# Adafruit_OV5640_Breakout.net
KiCad netlist of a schematic drawn in EAGLE
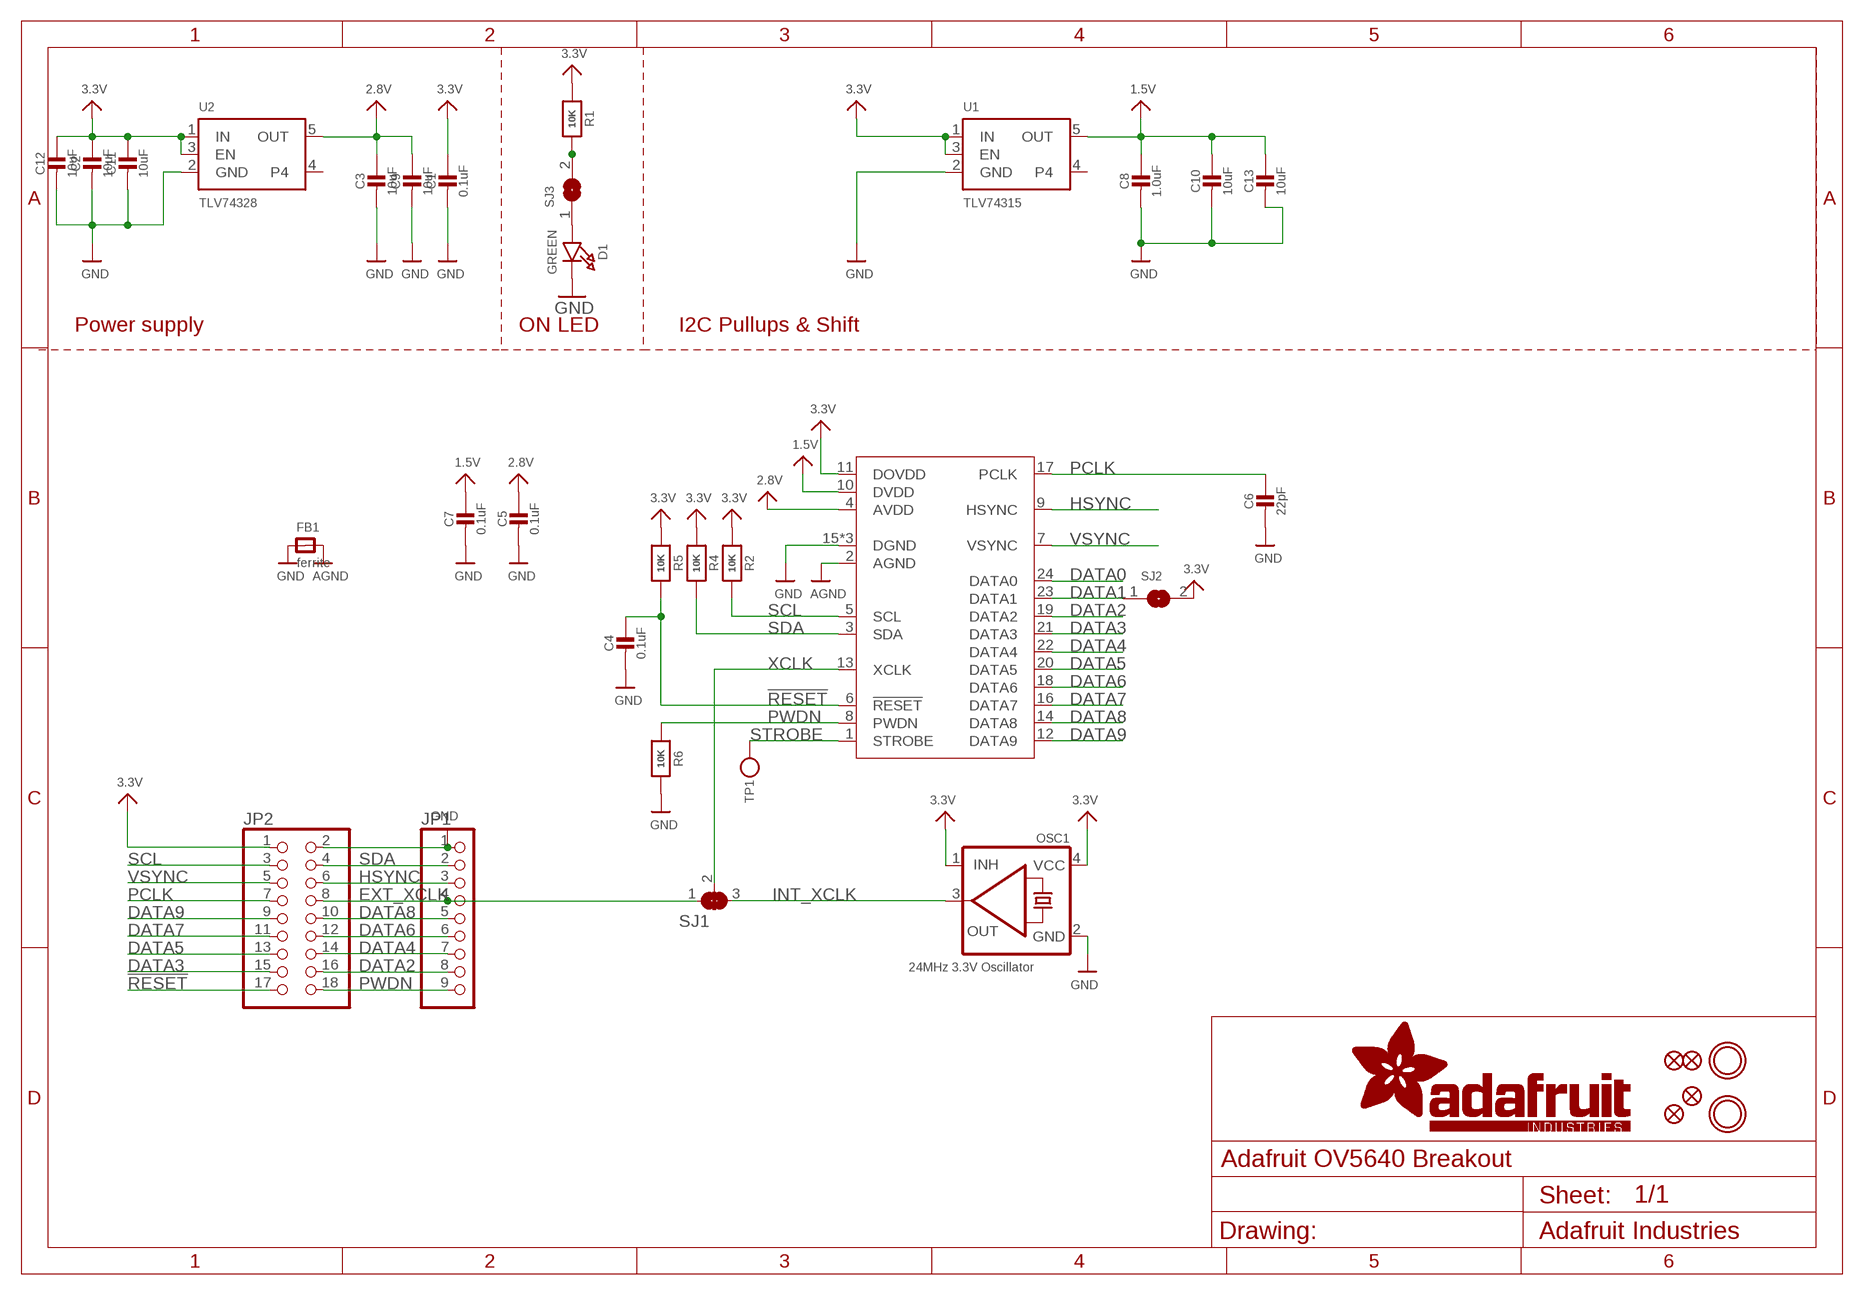
[diagram p0: schematic, sheet 1]

(export (version "E")
  (design (tool "Eeschema 10.0.6"))
  (components
    (comp (ref "C1")
      (value "0.1uF")
      (footprint "eagle-import:0603-NO")
      (libsource (lib "eagle-import") (part "CAP_CERAMIC0603_NO"))
    )
    (comp (ref "C2")
      (value "10uF")
      (footprint "eagle-import:0805-NO")
      (libsource (lib "eagle-import") (part "CAP_CERAMIC0805-NOOUTLINE"))
    )
    (comp (ref "C3")
      (value "10uF")
      (footprint "eagle-import:0805-NO")
      (libsource (lib "eagle-import") (part "CAP_CERAMIC0805-NOOUTLINE"))
    )
    (comp (ref "C4")
      (value "0.1uF")
      (footprint "eagle-import:0603-NO")
      (libsource (lib "eagle-import") (part "CAP_CERAMIC0603_NO"))
    )
    (comp (ref "C5")
      (value "0.1uF")
      (footprint "eagle-import:0603-NO")
      (libsource (lib "eagle-import") (part "CAP_CERAMIC0603_NO"))
    )
    (comp (ref "C6")
      (value "22pF")
      (footprint "eagle-import:0603-NO")
      (libsource (lib "eagle-import") (part "CAP_CERAMIC0603_NO"))
    )
    (comp (ref "C7")
      (value "0.1uF")
      (footprint "eagle-import:0603-NO")
      (libsource (lib "eagle-import") (part "CAP_CERAMIC0603_NO"))
    )
    (comp (ref "C8")
      (value "1.0uF")
      (footprint "eagle-import:0603-NO")
      (libsource (lib "eagle-import") (part "CAP_CERAMIC0603_NO"))
    )
    (comp (ref "C9")
      (value "10uF")
      (footprint "eagle-import:0805-NO")
      (libsource (lib "eagle-import") (part "CAP_CERAMIC0805-NOOUTLINE"))
    )
    (comp (ref "C10")
      (value "10uF")
      (footprint "eagle-import:0805-NO")
      (libsource (lib "eagle-import") (part "CAP_CERAMIC0805-NOOUTLINE"))
    )
    (comp (ref "C11")
      (value "10uF")
      (footprint "eagle-import:0805-NO")
      (libsource (lib "eagle-import") (part "CAP_CERAMIC0805-NOOUTLINE"))
    )
    (comp (ref "C12")
      (value "10uF")
      (footprint "eagle-import:0805-NO")
      (libsource (lib "eagle-import") (part "CAP_CERAMIC0805-NOOUTLINE"))
    )
    (comp (ref "C13")
      (value "10uF")
      (footprint "eagle-import:0805-NO")
      (libsource (lib "eagle-import") (part "CAP_CERAMIC0805-NOOUTLINE"))
    )
    (comp (ref "D1")
      (value "GREEN")
      (footprint "eagle-import:CHIPLED_0603_NOOUTLINE")
      (libsource (lib "eagle-import") (part "LED0603_NOOUTLINE"))
    )
    (comp (ref "FB1")
      (value "ferrite")
      (footprint "eagle-import:0603-NO")
      (libsource (lib "eagle-import") (part "FERRITE-0603NO"))
    )
    (comp (ref "FID1")
      (value "FIDUCIAL_1MM")
      (footprint "eagle-import:FIDUCIAL_1MM")
      (libsource (lib "eagle-import") (part "FIDUCIAL_1MM"))
    )
    (comp (ref "FID2")
      (value "FIDUCIAL_1MM")
      (footprint "eagle-import:FIDUCIAL_1MM")
      (libsource (lib "eagle-import") (part "FIDUCIAL_1MM"))
    )
    (comp (ref "FID3")
      (value "FIDUCIAL_1MM")
      (footprint "eagle-import:FIDUCIAL_1MM")
      (libsource (lib "eagle-import") (part "FIDUCIAL_1MM"))
    )
    (comp (ref "FID4")
      (value "FIDUCIAL_1MM")
      (footprint "eagle-import:FIDUCIAL_1MM")
      (libsource (lib "eagle-import") (part "FIDUCIAL_1MM"))
    )
    (comp (ref "JP1")
      (value "HEADER-1X970MIL")
      (footprint "eagle-import:1X09_ROUND_70")
      (libsource (lib "eagle-import") (part "HEADER-1X970MIL"))
    )
    (comp (ref "JP2")
      (value "PINHD-2X9-BIG")
      (footprint "eagle-import:2X09-BIG")
      (libsource (lib "eagle-import") (part "PINHD-2X9-BIG"))
    )
    (comp (ref "OSC1")
      (value "24MHz 3.3V Oscillator")
      (footprint "eagle-import:OSC_3.2X2.5MM")
      (libsource (lib "eagle-import") (part "OSCILLATOR3.2X2.5"))
    )
    (comp (ref "R1")
      (value "10K")
      (footprint "eagle-import:0603-NO")
      (libsource (lib "eagle-import") (part "RESISTOR_0603_NOOUT"))
    )
    (comp (ref "R2")
      (value "10K")
      (footprint "eagle-import:0603-NO")
      (libsource (lib "eagle-import") (part "RESISTOR_0603_NOOUT"))
    )
    (comp (ref "R4")
      (value "10K")
      (footprint "eagle-import:0603-NO")
      (libsource (lib "eagle-import") (part "RESISTOR_0603_NOOUT"))
    )
    (comp (ref "R5")
      (value "10K")
      (footprint "eagle-import:0603-NO")
      (libsource (lib "eagle-import") (part "RESISTOR_0603_NOOUT"))
    )
    (comp (ref "R6")
      (value "10K")
      (footprint "eagle-import:0603-NO")
      (libsource (lib "eagle-import") (part "RESISTOR_0603_NOOUT"))
    )
    (comp (ref "SJ1")
      (value "SOLDERJUMPER_2WAY")
      (footprint "eagle-import:SOLDERJUMPER_2WAY_OPEN_NOPASTE")
      (libsource (lib "eagle-import") (part "SOLDERJUMPER_2WAY"))
    )
    (comp (ref "SJ2")
      (value "SOLDERJUMPER")
      (footprint "eagle-import:SOLDERJUMPER_ARROW_NOPASTE")
      (libsource (lib "eagle-import") (part "SOLDERJUMPER"))
    )
    (comp (ref "SJ3")
      (value "SOLDERJUMPERCLOSED")
      (footprint "eagle-import:SOLDERJUMPER_CLOSEDWIRE")
      (libsource (lib "eagle-import") (part "SOLDERJUMPERCLOSED"))
    )
    (comp (ref "TP1")
      (value "TESTPOINTROUND1.5MM")
      (footprint "eagle-import:TESTPOINT_ROUND_1.5MM")
      (libsource (lib "eagle-import") (part "TESTPOINTROUND1.5MM"))
    )
    (comp (ref "U$1")
      (value "MOUNTINGHOLE3.0THIN")
      (footprint "eagle-import:MOUNTINGHOLE_3.0_PLATEDTHIN")
      (libsource (lib "eagle-import") (part "MOUNTINGHOLE3.0THIN"))
    )
    (comp (ref "U$17")
      (value "MOUNTINGHOLE3.0THIN")
      (footprint "eagle-import:MOUNTINGHOLE_3.0_PLATEDTHIN")
      (libsource (lib "eagle-import") (part "MOUNTINGHOLE3.0THIN"))
    )
    (comp (ref "U1")
      (value "TLV74315")
      (footprint "eagle-import:SOT23-5")
      (fields (field (name "JLC_ROTATION") "0"))
      (libsource (lib "eagle-import") (part "VREG_SOT23-5"))
    )
    (comp (ref "U2")
      (value "TLV74328")
      (footprint "eagle-import:SOT23-5")
      (fields (field (name "JLC_ROTATION") "0"))
      (libsource (lib "eagle-import") (part "VREG_SOT23-5"))
    )
    (comp (ref "X1")
      (value "CAMERA_OV2640")
      (footprint "eagle-import:OV2640FSL")
      (libsource (lib "eagle-import") (part "CAMERA_OV2640"))
    )
  )
  (nets
    (net (code "1") (name "/DATA0") (class "Default")
      (node (ref "X1") (pin "24") (pinfunction "DATA0_24") (pintype "output"))
    )
    (net (code "2") (name "/DATA1") (class "Default")
      (node (ref "SJ2") (pin "1") (pinfunction "1_1") (pintype "passive"))
      (node (ref "X1") (pin "23") (pinfunction "DATA1_23") (pintype "output"))
    )
    (net (code "3") (name "/DATA2") (class "Default")
      (node (ref "JP1") (pin "8") (pinfunction "8_8") (pintype "passive"))
      (node (ref "JP2") (pin "16") (pinfunction "16_16") (pintype "passive"))
      (node (ref "X1") (pin "19") (pinfunction "DATA2_19") (pintype "output"))
    )
    (net (code "4") (name "/DATA3") (class "Default")
      (node (ref "JP2") (pin "15") (pinfunction "15_15") (pintype "passive"))
      (node (ref "X1") (pin "21") (pinfunction "DATA3_21") (pintype "output"))
    )
    (net (code "5") (name "/DATA4") (class "Default")
      (node (ref "JP1") (pin "7") (pinfunction "7_7") (pintype "passive"))
      (node (ref "JP2") (pin "14") (pinfunction "14_14") (pintype "passive"))
      (node (ref "X1") (pin "22") (pinfunction "DATA4_22") (pintype "output"))
    )
    (net (code "6") (name "/DATA5") (class "Default")
      (node (ref "JP2") (pin "13") (pinfunction "13_13") (pintype "passive"))
      (node (ref "X1") (pin "20") (pinfunction "DATA5_20") (pintype "output"))
    )
    (net (code "7") (name "/DATA6") (class "Default")
      (node (ref "JP1") (pin "6") (pinfunction "6_6") (pintype "passive"))
      (node (ref "JP2") (pin "12") (pinfunction "12_12") (pintype "passive"))
      (node (ref "X1") (pin "18") (pinfunction "DATA6_18") (pintype "output"))
    )
    (net (code "8") (name "/DATA7") (class "Default")
      (node (ref "JP2") (pin "11") (pinfunction "11_11") (pintype "passive"))
      (node (ref "X1") (pin "16") (pinfunction "DATA7_16") (pintype "output"))
    )
    (net (code "9") (name "/DATA8") (class "Default")
      (node (ref "JP1") (pin "5") (pinfunction "5_5") (pintype "passive"))
      (node (ref "JP2") (pin "10") (pinfunction "10_10") (pintype "passive"))
      (node (ref "X1") (pin "14") (pinfunction "DATA8_14") (pintype "output"))
    )
    (net (code "10") (name "/DATA9") (class "Default")
      (node (ref "JP2") (pin "9") (pinfunction "9_9") (pintype "passive"))
      (node (ref "X1") (pin "12") (pinfunction "DATA9_12") (pintype "output"))
    )
    (net (code "11") (name "/EXT_XCLK") (class "Default")
      (node (ref "JP1") (pin "4") (pinfunction "4_4") (pintype "passive"))
      (node (ref "JP2") (pin "8") (pinfunction "8_8") (pintype "passive"))
      (node (ref "SJ1") (pin "1") (pinfunction "1_1") (pintype "passive"))
    )
    (net (code "12") (name "/HSYNC") (class "Default")
      (node (ref "JP1") (pin "3") (pinfunction "3_3") (pintype "passive"))
      (node (ref "JP2") (pin "6") (pinfunction "6_6") (pintype "passive"))
      (node (ref "X1") (pin "9") (pinfunction "HSYNC_9") (pintype "output"))
    )
    (net (code "13") (name "/INT_XCLK") (class "Default")
      (node (ref "OSC1") (pin "3") (pinfunction "OUT_3") (pintype "output"))
      (node (ref "SJ1") (pin "3") (pinfunction "3_3") (pintype "passive"))
    )
    (net (code "14") (name "/PCLK") (class "Default")
      (node (ref "C6") (pin "1") (pinfunction "1_1") (pintype "passive"))
      (node (ref "JP2") (pin "7") (pinfunction "7_7") (pintype "passive"))
      (node (ref "X1") (pin "17") (pinfunction "PCLK_17") (pintype "output"))
    )
    (net (code "15") (name "/PWDN") (class "Default")
      (node (ref "JP1") (pin "9") (pinfunction "9_9") (pintype "passive"))
      (node (ref "JP2") (pin "18") (pinfunction "18_18") (pintype "passive"))
      (node (ref "R6") (pin "1") (pinfunction "1_1") (pintype "passive"))
      (node (ref "X1") (pin "8") (pinfunction "PWDN_8") (pintype "input"))
    )
    (net (code "16") (name "/SCL") (class "Default")
      (node (ref "JP2") (pin "3") (pinfunction "3_3") (pintype "passive"))
      (node (ref "R2") (pin "2") (pinfunction "2_2") (pintype "passive"))
      (node (ref "X1") (pin "5") (pinfunction "SCL_5") (pintype "bidirectional"))
    )
    (net (code "17") (name "/SDA") (class "Default")
      (node (ref "JP1") (pin "2") (pinfunction "2_2") (pintype "passive"))
      (node (ref "JP2") (pin "4") (pinfunction "4_4") (pintype "passive"))
      (node (ref "R4") (pin "2") (pinfunction "2_2") (pintype "passive"))
      (node (ref "X1") (pin "3") (pinfunction "SDA_3") (pintype "bidirectional"))
    )
    (net (code "18") (name "/STROBE") (class "Default")
      (node (ref "TP1") (pin "P$1") (pinfunction "P$1_P$1") (pintype "bidirectional"))
      (node (ref "X1") (pin "1") (pinfunction "STROBE_1") (pintype "input"))
    )
    (net (code "19") (name "/VSYNC") (class "Default")
      (node (ref "JP2") (pin "5") (pinfunction "5_5") (pintype "passive"))
      (node (ref "X1") (pin "7") (pinfunction "VSYNC_7") (pintype "output"))
    )
    (net (code "20") (name "/XCLK") (class "Default")
      (node (ref "SJ1") (pin "2") (pinfunction "2_2") (pintype "passive"))
      (node (ref "X1") (pin "13") (pinfunction "XCLK_13") (pintype "input"))
    )
    (net (code "21") (name "/~{RESET}") (class "Default")
      (node (ref "C4") (pin "1") (pinfunction "1_1") (pintype "passive"))
      (node (ref "JP2") (pin "17") (pinfunction "17_17") (pintype "passive"))
      (node (ref "R5") (pin "2") (pinfunction "2_2") (pintype "passive"))
      (node (ref "X1") (pin "6") (pinfunction "~{RESET}_6") (pintype "input"))
    )
    (net (code "22") (name "1.5V") (class "Default")
      (node (ref "C10") (pin "1") (pinfunction "1_1") (pintype "passive"))
      (node (ref "C13") (pin "1") (pinfunction "1_1") (pintype "passive"))
      (node (ref "C7") (pin "1") (pinfunction "1_1") (pintype "passive"))
      (node (ref "C8") (pin "1") (pinfunction "1_1") (pintype "passive"))
      (node (ref "U1") (pin "5") (pinfunction "OUT_5") (pintype "power_in"))
      (node (ref "X1") (pin "10") (pinfunction "DVDD_10") (pintype "power_in"))
    )
    (net (code "23") (name "2.8V") (class "Default")
      (node (ref "C3") (pin "1") (pinfunction "1_1") (pintype "passive"))
      (node (ref "C5") (pin "1") (pinfunction "1_1") (pintype "passive"))
      (node (ref "C9") (pin "1") (pinfunction "1_1") (pintype "passive"))
      (node (ref "U2") (pin "5") (pinfunction "OUT_5") (pintype "power_in"))
      (node (ref "X1") (pin "4") (pinfunction "AVDD_4") (pintype "power_in"))
    )
    (net (code "24") (name "3.3V") (class "Default")
      (node (ref "C1") (pin "1") (pinfunction "1_1") (pintype "passive"))
      (node (ref "C11") (pin "1") (pinfunction "1_1") (pintype "passive"))
      (node (ref "C12") (pin "1") (pinfunction "1_1") (pintype "passive"))
      (node (ref "C2") (pin "1") (pinfunction "1_1") (pintype "passive"))
      (node (ref "JP2") (pin "1") (pinfunction "1_1") (pintype "passive"))
      (node (ref "OSC1") (pin "1") (pinfunction "INH_1") (pintype "bidirectional"))
      (node (ref "OSC1") (pin "4") (pinfunction "VCC_4") (pintype "power_in"))
      (node (ref "R1") (pin "1") (pinfunction "1_1") (pintype "passive"))
      (node (ref "R2") (pin "1") (pinfunction "1_1") (pintype "passive"))
      (node (ref "R4") (pin "1") (pinfunction "1_1") (pintype "passive"))
      (node (ref "R5") (pin "1") (pinfunction "1_1") (pintype "passive"))
      (node (ref "SJ2") (pin "2") (pinfunction "2_2") (pintype "passive"))
      (node (ref "U1") (pin "1") (pinfunction "IN_1") (pintype "power_in"))
      (node (ref "U1") (pin "3") (pinfunction "EN_3") (pintype "input"))
      (node (ref "U2") (pin "1") (pinfunction "IN_1") (pintype "power_in"))
      (node (ref "U2") (pin "3") (pinfunction "EN_3") (pintype "input"))
      (node (ref "X1") (pin "11") (pinfunction "DOVDD_11") (pintype "power_in"))
    )
    (net (code "25") (name "AGND") (class "Default")
      (node (ref "FB1") (pin "2") (pinfunction "P$2_2") (pintype "passive"))
      (node (ref "X1") (pin "2") (pinfunction "AGND_2") (pintype "power_in"))
    )
    (net (code "26") (name "GND") (class "Default")
      (node (ref "C1") (pin "2") (pinfunction "2_2") (pintype "passive"))
      (node (ref "C10") (pin "2") (pinfunction "2_2") (pintype "passive"))
      (node (ref "C11") (pin "2") (pinfunction "2_2") (pintype "passive"))
      (node (ref "C12") (pin "2") (pinfunction "2_2") (pintype "passive"))
      (node (ref "C13") (pin "2") (pinfunction "2_2") (pintype "passive"))
      (node (ref "C2") (pin "2") (pinfunction "2_2") (pintype "passive"))
      (node (ref "C3") (pin "2") (pinfunction "2_2") (pintype "passive"))
      (node (ref "C4") (pin "2") (pinfunction "2_2") (pintype "passive"))
      (node (ref "C5") (pin "2") (pinfunction "2_2") (pintype "passive"))
      (node (ref "C6") (pin "2") (pinfunction "2_2") (pintype "passive"))
      (node (ref "C7") (pin "2") (pinfunction "2_2") (pintype "passive"))
      (node (ref "C8") (pin "2") (pinfunction "2_2") (pintype "passive"))
      (node (ref "C9") (pin "2") (pinfunction "2_2") (pintype "passive"))
      (node (ref "D1") (pin "C") (pinfunction "C_C") (pintype "passive"))
      (node (ref "FB1") (pin "1") (pinfunction "P$1_1") (pintype "passive"))
      (node (ref "JP1") (pin "1") (pinfunction "1_1") (pintype "passive"))
      (node (ref "JP2") (pin "2") (pinfunction "2_2") (pintype "passive"))
      (node (ref "OSC1") (pin "2") (pinfunction "GND_2") (pintype "power_in"))
      (node (ref "R6") (pin "2") (pinfunction "2_2") (pintype "passive"))
      (node (ref "U1") (pin "2") (pinfunction "GND_2") (pintype "power_in"))
      (node (ref "U2") (pin "2") (pinfunction "GND_2") (pintype "power_in"))
      (node (ref "X1") (pin "15") (pinfunction "DGND_15") (pintype "power_in"))
      (node (ref "X1") (pin "SPRT1") (pinfunction "DGND_SPRT1") (pintype "power_in"))
      (node (ref "X1") (pin "SPRT2") (pinfunction "DGND_SPRT2") (pintype "power_in"))
    )
    (net (code "27") (name "Net-(D1-PadA)") (class "Default")
      (node (ref "D1") (pin "A") (pinfunction "A_A") (pintype "passive"))
      (node (ref "SJ3") (pin "1") (pinfunction "1_1") (pintype "passive"))
    )
    (net (code "28") (name "Net-(R1-Pad2)") (class "Default")
      (node (ref "R1") (pin "2") (pinfunction "2_2") (pintype "passive"))
      (node (ref "SJ3") (pin "2") (pinfunction "2_2") (pintype "passive"))
    )
    (net (code "29") (name "unconnected-(U1-P4-Pad4)") (class "Default")
      (node (ref "U1") (pin "4") (pinfunction "P4_4") (pintype "bidirectional"))
    )
    (net (code "30") (name "unconnected-(U2-P4-Pad4)") (class "Default")
      (node (ref "U2") (pin "4") (pinfunction "P4_4") (pintype "bidirectional"))
    )
  )
)
